# smarTag_v02.net
KiCad netlist of a schematic drawn in EAGLE
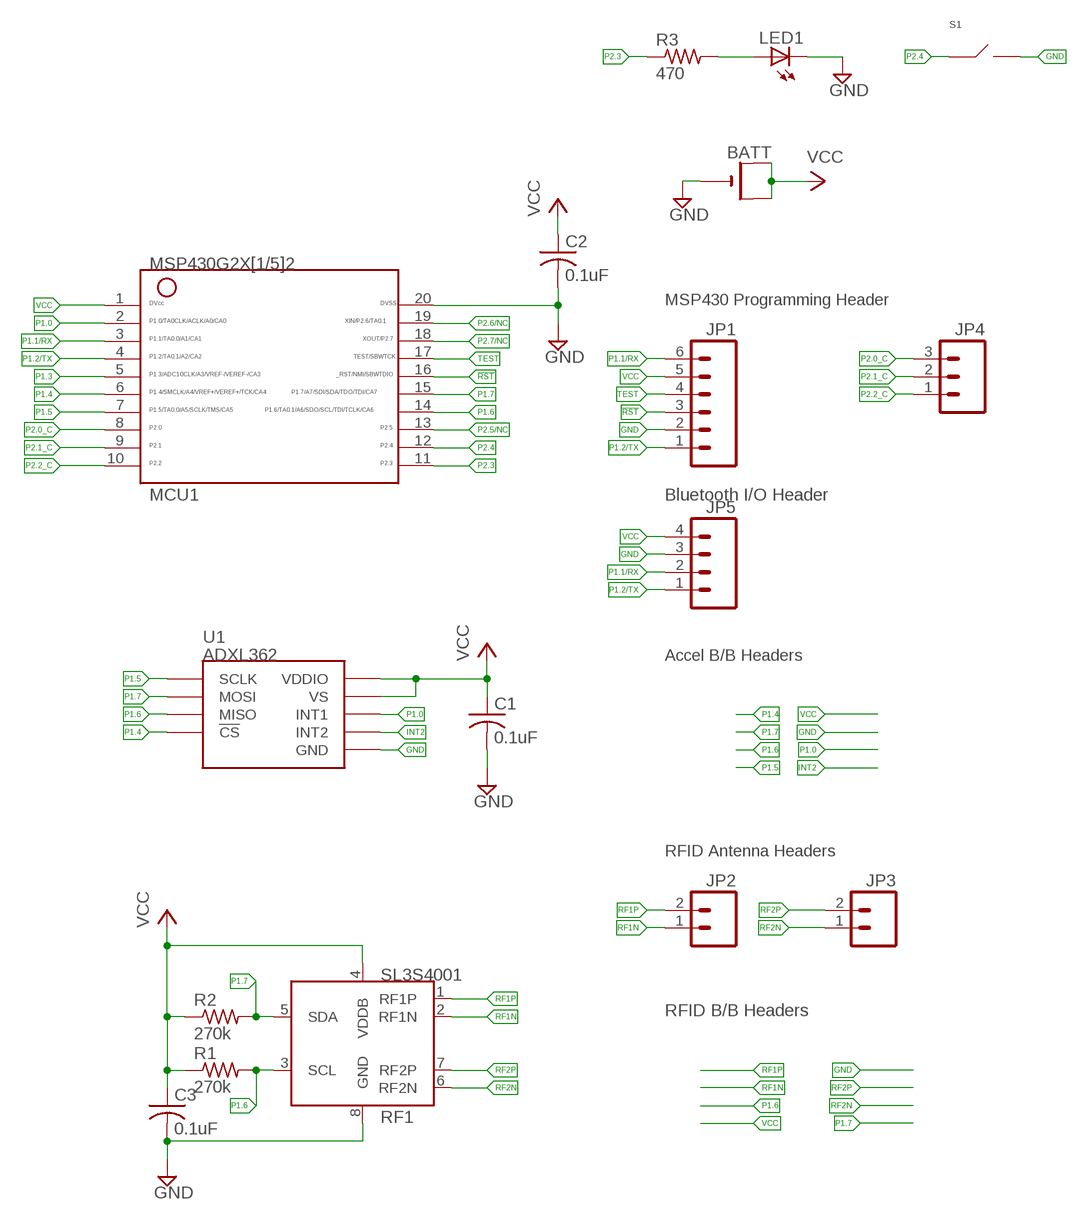
[diagram p0: schematic, sheet 1]

(export (version "E")
  (design (tool "Eeschema 10.0.6"))
  (components
    (comp (ref "BATT")
      (value "CR2032SMT")
      (footprint "eagle-import:CR2032-SMD")
      (libsource (lib "eagle-import") (part "CR2032SMT"))
    )
    (comp (ref "C1")
      (value "0.1uF")
      (footprint "eagle-import:C0805")
      (libsource (lib "eagle-import") (part "C-USC0805"))
    )
    (comp (ref "C2")
      (value "0.1uF")
      (footprint "eagle-import:C0805K")
      (libsource (lib "eagle-import") (part "C-USC0805K"))
    )
    (comp (ref "C3")
      (value "0.1uF")
      (footprint "eagle-import:C0805")
      (libsource (lib "eagle-import") (part "C-USC0805"))
    )
    (comp (ref "JP1")
      (value "M061.27MM")
      (footprint "eagle-import:1X06-1.27MM")
      (libsource (lib "eagle-import") (part "M061.27MM"))
    )
    (comp (ref "JP2")
      (value "M02LOCK")
      (footprint "eagle-import:1X02_LOCK")
      (libsource (lib "eagle-import") (part "M02LOCK"))
    )
    (comp (ref "JP3")
      (value "M02LOCK")
      (footprint "eagle-import:1X02_LOCK")
      (libsource (lib "eagle-import") (part "M02LOCK"))
    )
    (comp (ref "JP4")
      (value "M03LOCK")
      (footprint "eagle-import:1X03_LOCK")
      (libsource (lib "eagle-import") (part "M03LOCK"))
    )
    (comp (ref "JP5")
      (value "M04LOCK")
      (footprint "eagle-import:1X04_LOCK")
      (libsource (lib "eagle-import") (part "M04LOCK"))
    )
    (comp (ref "LED1")
      (value "LEDCHIP-LED0805")
      (footprint "eagle-import:CHIP-LED0805")
      (libsource (lib "eagle-import") (part "LEDCHIP-LED0805"))
    )
    (comp (ref "MCU1")
      (value "G2X[1/5]2---PW20")
      (footprint "eagle-import:PW20")
      (libsource (lib "eagle-import") (part "G2X[1/5]2---PW20"))
    )
    (comp (ref "R1")
      (value "270k")
      (footprint "eagle-import:R0805")
      (libsource (lib "eagle-import") (part "R-US_R0805"))
    )
    (comp (ref "R2")
      (value "270k")
      (footprint "eagle-import:R0805")
      (libsource (lib "eagle-import") (part "R-US_R0805"))
    )
    (comp (ref "R3")
      (value "470")
      (footprint "eagle-import:R0805")
      (libsource (lib "eagle-import") (part "R-US_R0805"))
    )
    (comp (ref "RF1")
      (value "SL3S4001")
      (footprint "eagle-import:SOT902-1_2_3")
      (libsource (lib "eagle-import") (part "SL3S4001"))
    )
    (comp (ref "S1")
      (value "SPST_B3FS-1000")
      (footprint "eagle-import:B3FS-1000")
      (libsource (lib "eagle-import") (part "SPST_B3FS-1000"))
    )
    (comp (ref "U1")
      (value "ADXL362")
      (footprint "eagle-import:ADXL362")
      (libsource (lib "eagle-import") (part "ADXL362"))
    )
  )
  (nets
    (net (code "1") (name "/~{RST}") (class "Default")
      (node (ref "JP1") (pin "3") (pinfunction "3_3") (pintype "passive"))
      (node (ref "MCU1") (pin "16") (pinfunction "16_16") (pintype "bidirectional"))
    )
    (net (code "2") (name "GND") (class "Default")
      (node (ref "BATT") (pin "-") (pinfunction "-_-") (pintype "passive"))
      (node (ref "C1") (pin "2") (pinfunction "2_2") (pintype "passive"))
      (node (ref "C2") (pin "2") (pinfunction "2_2") (pintype "passive"))
      (node (ref "C3") (pin "2") (pinfunction "2_2") (pintype "passive"))
      (node (ref "JP1") (pin "2") (pinfunction "2_2") (pintype "passive"))
      (node (ref "JP5") (pin "3") (pinfunction "3_3") (pintype "passive"))
      (node (ref "LED1") (pin "C") (pinfunction "C_C") (pintype "passive"))
      (node (ref "MCU1") (pin "20") (pinfunction "20_20") (pintype "bidirectional"))
      (node (ref "RF1") (pin "8") (pinfunction "GND_8") (pintype "power_in"))
      (node (ref "S1") (pin "3") (pinfunction "B_3") (pintype "bidirectional"))
      (node (ref "S1") (pin "4") (pinfunction "B_4") (pintype "bidirectional"))
      (node (ref "U1") (pin "P$12") (pinfunction "GND_P$12") (pintype "bidirectional"))
      (node (ref "U1") (pin "P$13") (pinfunction "GND_P$13") (pintype "bidirectional"))
      (node (ref "U1") (pin "P$16") (pinfunction "GND_P$16") (pintype "bidirectional"))
    )
    (net (code "3") (name "INT2") (class "Default")
      (node (ref "U1") (pin "P$9") (pinfunction "INT2_P$9") (pintype "bidirectional"))
    )
    (net (code "4") (name "Net-(LED1-PadA)") (class "Default")
      (node (ref "LED1") (pin "A") (pinfunction "A_A") (pintype "passive"))
      (node (ref "R3") (pin "2") (pinfunction "2_2") (pintype "passive"))
    )
    (net (code "5") (name "P1.0") (class "Default")
      (node (ref "MCU1") (pin "2") (pinfunction "2_2") (pintype "bidirectional"))
      (node (ref "U1") (pin "P$11") (pinfunction "INT1_P$11") (pintype "bidirectional"))
    )
    (net (code "6") (name "P1.1{slash}RX") (class "Default")
      (node (ref "JP1") (pin "6") (pinfunction "6_6") (pintype "passive"))
      (node (ref "JP5") (pin "2") (pinfunction "2_2") (pintype "passive"))
      (node (ref "MCU1") (pin "3") (pinfunction "3_3") (pintype "bidirectional"))
    )
    (net (code "7") (name "P1.2{slash}TX") (class "Default")
      (node (ref "JP1") (pin "1") (pinfunction "1_1") (pintype "passive"))
      (node (ref "JP5") (pin "1") (pinfunction "1_1") (pintype "passive"))
      (node (ref "MCU1") (pin "4") (pinfunction "4_4") (pintype "bidirectional"))
    )
    (net (code "8") (name "P1.3") (class "Default")
      (node (ref "MCU1") (pin "5") (pinfunction "5_5") (pintype "bidirectional"))
    )
    (net (code "9") (name "P1.4") (class "Default")
      (node (ref "MCU1") (pin "6") (pinfunction "6_6") (pintype "bidirectional"))
      (node (ref "U1") (pin "P$8") (pinfunction "~{CS}_P$8") (pintype "bidirectional"))
    )
    (net (code "10") (name "P1.5") (class "Default")
      (node (ref "MCU1") (pin "7") (pinfunction "7_7") (pintype "bidirectional"))
      (node (ref "U1") (pin "P$4") (pinfunction "SCLK_P$4") (pintype "bidirectional"))
    )
    (net (code "11") (name "P1.6") (class "Default")
      (node (ref "MCU1") (pin "14") (pinfunction "14_14") (pintype "bidirectional"))
      (node (ref "R1") (pin "2") (pinfunction "2_2") (pintype "passive"))
      (node (ref "RF1") (pin "3") (pinfunction "SCL_3") (pintype "bidirectional"))
      (node (ref "U1") (pin "P$7") (pinfunction "MISO_P$7") (pintype "bidirectional"))
    )
    (net (code "12") (name "P1.7") (class "Default")
      (node (ref "MCU1") (pin "15") (pinfunction "15_15") (pintype "bidirectional"))
      (node (ref "R2") (pin "2") (pinfunction "2_2") (pintype "passive"))
      (node (ref "RF1") (pin "5") (pinfunction "SDA_5") (pintype "bidirectional"))
      (node (ref "U1") (pin "P$6") (pinfunction "MOSI_P$6") (pintype "bidirectional"))
    )
    (net (code "13") (name "P2.0_C") (class "Default")
      (node (ref "JP4") (pin "3") (pinfunction "3_3") (pintype "passive"))
      (node (ref "MCU1") (pin "8") (pinfunction "8_8") (pintype "bidirectional"))
    )
    (net (code "14") (name "P2.1_C") (class "Default")
      (node (ref "JP4") (pin "2") (pinfunction "2_2") (pintype "passive"))
      (node (ref "MCU1") (pin "9") (pinfunction "9_9") (pintype "bidirectional"))
    )
    (net (code "15") (name "P2.2_C") (class "Default")
      (node (ref "JP4") (pin "1") (pinfunction "1_1") (pintype "passive"))
      (node (ref "MCU1") (pin "10") (pinfunction "10_10") (pintype "bidirectional"))
    )
    (net (code "16") (name "P2.3") (class "Default")
      (node (ref "MCU1") (pin "11") (pinfunction "11_11") (pintype "bidirectional"))
      (node (ref "R3") (pin "1") (pinfunction "1_1") (pintype "passive"))
    )
    (net (code "17") (name "P2.4") (class "Default")
      (node (ref "MCU1") (pin "12") (pinfunction "12_12") (pintype "bidirectional"))
      (node (ref "S1") (pin "1") (pinfunction "A_1") (pintype "bidirectional"))
      (node (ref "S1") (pin "2") (pinfunction "A_2") (pintype "bidirectional"))
    )
    (net (code "18") (name "P2.5{slash}NC") (class "Default")
      (node (ref "MCU1") (pin "13") (pinfunction "13_13") (pintype "bidirectional"))
    )
    (net (code "19") (name "P2.6{slash}NC") (class "Default")
      (node (ref "MCU1") (pin "19") (pinfunction "19_19") (pintype "bidirectional"))
    )
    (net (code "20") (name "P2.7{slash}NC") (class "Default")
      (node (ref "MCU1") (pin "18") (pinfunction "18_18") (pintype "bidirectional"))
    )
    (net (code "21") (name "RF1N") (class "Default")
      (node (ref "JP2") (pin "1") (pinfunction "1_1") (pintype "passive"))
      (node (ref "RF1") (pin "2") (pinfunction "RF1N_2") (pintype "passive"))
    )
    (net (code "22") (name "RF1P") (class "Default")
      (node (ref "JP2") (pin "2") (pinfunction "2_2") (pintype "passive"))
      (node (ref "RF1") (pin "1") (pinfunction "RF1P_1") (pintype "passive"))
    )
    (net (code "23") (name "RF2N") (class "Default")
      (node (ref "JP3") (pin "1") (pinfunction "1_1") (pintype "passive"))
      (node (ref "RF1") (pin "6") (pinfunction "RF2N_6") (pintype "passive"))
    )
    (net (code "24") (name "RF2P") (class "Default")
      (node (ref "JP3") (pin "2") (pinfunction "2_2") (pintype "passive"))
      (node (ref "RF1") (pin "7") (pinfunction "RF2P_7") (pintype "passive"))
    )
    (net (code "25") (name "TEST") (class "Default")
      (node (ref "JP1") (pin "4") (pinfunction "4_4") (pintype "passive"))
      (node (ref "MCU1") (pin "17") (pinfunction "17_17") (pintype "bidirectional"))
    )
    (net (code "26") (name "VCC") (class "Default")
      (node (ref "BATT") (pin "+$1") (pinfunction "+_+$1") (pintype "passive"))
      (node (ref "BATT") (pin "+$2") (pinfunction "+1_+$2") (pintype "passive"))
      (node (ref "C1") (pin "1") (pinfunction "1_1") (pintype "passive"))
      (node (ref "C2") (pin "1") (pinfunction "1_1") (pintype "passive"))
      (node (ref "C3") (pin "1") (pinfunction "1_1") (pintype "passive"))
      (node (ref "JP1") (pin "5") (pinfunction "5_5") (pintype "passive"))
      (node (ref "JP5") (pin "4") (pinfunction "4_4") (pintype "passive"))
      (node (ref "MCU1") (pin "1") (pinfunction "1_1") (pintype "bidirectional"))
      (node (ref "R1") (pin "1") (pinfunction "1_1") (pintype "passive"))
      (node (ref "R2") (pin "1") (pinfunction "1_1") (pintype "passive"))
      (node (ref "RF1") (pin "4") (pinfunction "VDDB_4") (pintype "power_in"))
      (node (ref "U1") (pin "P$1") (pinfunction "VDDIO_P$1") (pintype "bidirectional"))
      (node (ref "U1") (pin "P$14") (pinfunction "VS_P$14") (pintype "bidirectional"))
    )
  )
)
